# Scheme.net
KiCad netlist of a schematic drawn in Altium Designer
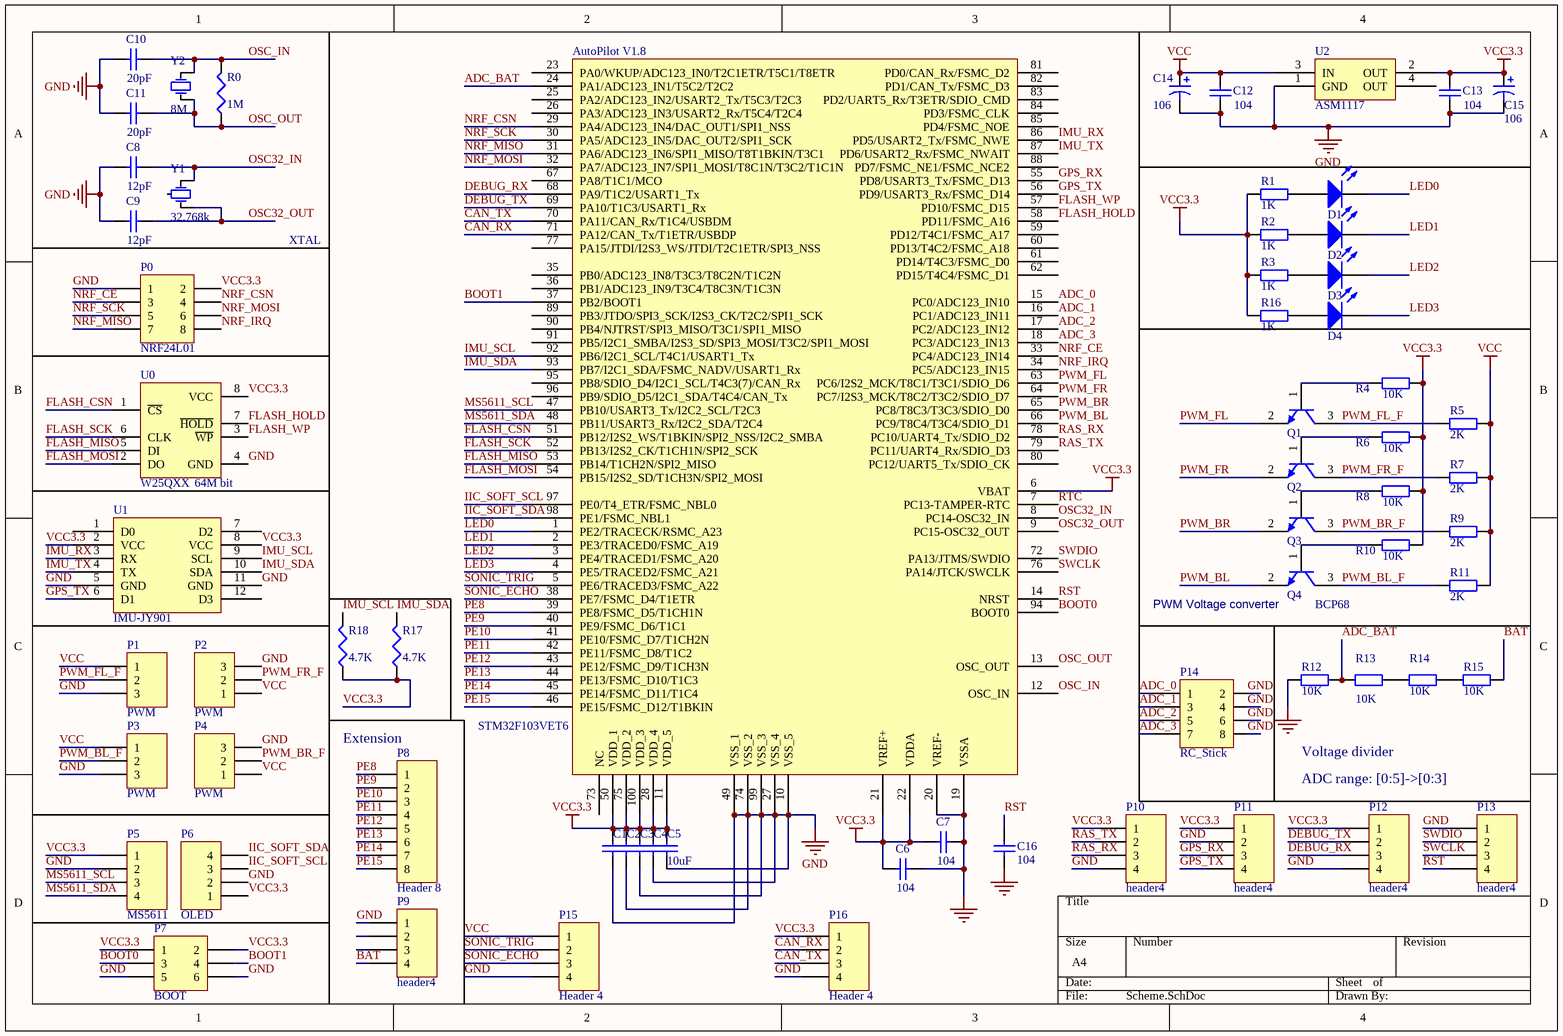
[diagram p0: Scheme.SchDoc]

(export (version "E")
  (design (tool "Eeschema 10.0.6"))
  (components
    (comp (ref "AutoPilot V1.8")
      (value "STM32F103VET6")
      (footprint "LQFP-100_M")
      (description "STM32单片机100引脚")
      (libsource (lib "LYY") (part "STM32F103V"))
    )
    (comp (ref "C1")
      (value "Cap Semi")
      (footprint "1608[0603]")
      (description "Capacitor (Semiconductor SIM Model)")
      (fields (field (name "PUBLISHER") "Altium Limited"))
      (libsource (lib "Miscellaneous Devices") (part "Cap Semi"))
    )
    (comp (ref "C2")
      (value "Cap Semi")
      (footprint "1608[0603]")
      (description "Capacitor (Semiconductor SIM Model)")
      (fields (field (name "PUBLISHER") "Altium Limited"))
      (libsource (lib "Miscellaneous Devices") (part "Cap Semi"))
    )
    (comp (ref "C3")
      (value "Cap Semi")
      (footprint "1608[0603]")
      (description "Capacitor (Semiconductor SIM Model)")
      (fields (field (name "PUBLISHER") "Altium Limited"))
      (libsource (lib "Miscellaneous Devices") (part "Cap Semi"))
    )
    (comp (ref "C4")
      (value "Cap Semi")
      (footprint "1608[0603]")
      (description "Capacitor (Semiconductor SIM Model)")
      (fields (field (name "PUBLISHER") "Altium Limited"))
      (libsource (lib "Miscellaneous Devices") (part "Cap Semi"))
    )
    (comp (ref "C5")
      (value "10uF")
      (footprint "1608[0603]")
      (description "Capacitor (Semiconductor SIM Model)")
      (fields (field (name "Comment") "Cap Semi") (field (name "PUBLISHER") "Altium Limited"))
      (libsource (lib "Miscellaneous Devices") (part "Cap Semi"))
    )
    (comp (ref "C6")
      (value "104")
      (footprint "1608[0603]")
      (description "Capacitor (Semiconductor SIM Model)")
      (fields (field (name "Comment") "Cap Semi") (field (name "PUBLISHER") "Altium Limited"))
      (libsource (lib "Miscellaneous Devices") (part "Cap Semi"))
    )
    (comp (ref "C7")
      (value "104")
      (footprint "1608[0603]")
      (description "Capacitor (Semiconductor SIM Model)")
      (fields (field (name "Comment") "Cap Semi") (field (name "PUBLISHER") "Altium Limited"))
      (libsource (lib "Miscellaneous Devices") (part "Cap Semi"))
    )
    (comp (ref "C8")
      (value "12pF")
      (footprint "1608[0603]")
      (description "Capacitor (Semiconductor SIM Model)")
      (fields (field (name "Comment") "Cap Semi") (field (name "PUBLISHER") "Altium Limited"))
      (libsource (lib "Miscellaneous Devices") (part "Cap Semi"))
    )
    (comp (ref "C9")
      (value "12pF")
      (footprint "1608[0603]")
      (description "Capacitor (Semiconductor SIM Model)")
      (fields (field (name "Comment") "Cap Semi") (field (name "PUBLISHER") "Altium Limited"))
      (libsource (lib "Miscellaneous Devices") (part "Cap Semi"))
    )
    (comp (ref "C10")
      (value "20pF")
      (footprint "1608[0603]")
      (description "Capacitor (Semiconductor SIM Model)")
      (fields (field (name "Comment") "Cap Semi") (field (name "PUBLISHER") "Altium Limited"))
      (libsource (lib "Miscellaneous Devices") (part "Cap Semi"))
    )
    (comp (ref "C11")
      (value "20pF")
      (footprint "1608[0603]")
      (description "Capacitor (Semiconductor SIM Model)")
      (fields (field (name "Comment") "Cap Semi") (field (name "PUBLISHER") "Altium Limited"))
      (libsource (lib "Miscellaneous Devices") (part "Cap Semi"))
    )
    (comp (ref "C12")
      (value "104")
      (footprint "1608[0603]")
      (description "Capacitor (Semiconductor SIM Model)")
      (fields (field (name "Comment") "Cap Semi") (field (name "PUBLISHER") "Altium Limited"))
      (libsource (lib "Miscellaneous Devices") (part "Cap Semi"))
    )
    (comp (ref "C13")
      (value "104")
      (footprint "1608[0603]")
      (description "Capacitor (Semiconductor SIM Model)")
      (fields (field (name "Comment") "Cap Semi") (field (name "PUBLISHER") "Altium Limited"))
      (libsource (lib "Miscellaneous Devices") (part "Cap Semi"))
    )
    (comp (ref "C14")
      (value "106")
      (footprint "1812")
      (description "Polarized Capacitor (Surface Mount)")
      (fields (field (name "Comment") "Cap Pol3") (field (name "PUBLISHER") "Altium Limited"))
      (libsource (lib "Miscellaneous Devices") (part "Cap Pol3"))
    )
    (comp (ref "C15")
      (value "106")
      (footprint "1812")
      (description "Polarized Capacitor (Surface Mount)")
      (fields (field (name "Comment") "Cap Pol3") (field (name "PUBLISHER") "Altium Limited"))
      (libsource (lib "Miscellaneous Devices") (part "Cap Pol3"))
    )
    (comp (ref "C16")
      (value "104")
      (footprint "1608[0603]")
      (description "Capacitor (Semiconductor SIM Model)")
      (fields (field (name "Comment") "Cap Semi") (field (name "PUBLISHER") "Altium Limited"))
      (libsource (lib "Miscellaneous Devices") (part "Cap Semi"))
    )
    (comp (ref "D1")
      (value "LED0")
      (footprint "LED_0805")
      (description "发光二极管")
      (fields (field (name "PUBLISHER") "Altium Limited"))
      (libsource (lib "LYY") (part "LED0"))
    )
    (comp (ref "D2")
      (value "LED0")
      (footprint "LED_0805")
      (description "发光二极管")
      (fields (field (name "PUBLISHER") "Altium Limited"))
      (libsource (lib "LYY") (part "LED0"))
    )
    (comp (ref "D3")
      (value "LED0")
      (footprint "LED_0805")
      (description "发光二极管")
      (fields (field (name "PUBLISHER") "Altium Limited"))
      (libsource (lib "LYY") (part "LED0"))
    )
    (comp (ref "D4")
      (value "LED0")
      (footprint "LED_0805")
      (description "发光二极管")
      (fields (field (name "PUBLISHER") "Altium Limited"))
      (libsource (lib "LYY") (part "LED0"))
    )
    (comp (ref "P0")
      (value "NRF24L01")
      (footprint "HDR2X4")
      (description "Header, 4-Pin, Dual row")
      (fields (field (name "PUBLISHER") "Altium Limited"))
      (libsource (lib "Miscellaneous Connectors") (part "Header 4X2"))
    )
    (comp (ref "P1")
      (value "PWM")
      (footprint "HDR1X3")
      (description "Header, 3-Pin")
      (fields (field (name "PUBLISHER") "Altium Limited"))
      (libsource (lib "Miscellaneous Connectors") (part "Header 3"))
    )
    (comp (ref "P2")
      (value "PWM")
      (footprint "HDR1X3")
      (description "Header, 3-Pin")
      (fields (field (name "PUBLISHER") "Altium Limited"))
      (libsource (lib "") (part "Header 3_1"))
    )
    (comp (ref "P3")
      (value "PWM")
      (footprint "HDR1X3")
      (description "Header, 3-Pin")
      (fields (field (name "PUBLISHER") "Altium Limited"))
      (libsource (lib "Miscellaneous Connectors") (part "Header 3"))
    )
    (comp (ref "P4")
      (value "PWM")
      (footprint "HDR1X3")
      (description "Header, 3-Pin")
      (fields (field (name "PUBLISHER") "Altium Limited"))
      (libsource (lib "") (part "Header 3_1"))
    )
    (comp (ref "P5")
      (value "MS5611")
      (footprint "HDR1X4")
      (description "Header, 4-Pin")
      (fields (field (name "PUBLISHER") "Altium Limited"))
      (libsource (lib "Miscellaneous Connectors") (part "Header 4"))
    )
    (comp (ref "P6")
      (value "OLED")
      (footprint "HDR1X4")
      (description "Header, 4-Pin")
      (fields (field (name "PUBLISHER") "Altium Limited"))
      (libsource (lib "") (part "Header 4_1"))
    )
    (comp (ref "P7")
      (value "BOOT")
      (footprint "HDR2X3")
      (description "Header, 3-Pin, Dual row")
      (fields (field (name "PUBLISHER") "Altium Limited"))
      (libsource (lib "Miscellaneous Connectors") (part "Header 3X2"))
    )
    (comp (ref "P8")
      (value "Header 8")
      (footprint "HDR1X8")
      (description "Header, 8-Pin")
      (fields (field (name "PUBLISHER") "Altium Limited"))
      (libsource (lib "Miscellaneous Connectors") (part "Header 8"))
    )
    (comp (ref "P9")
      (value "header4")
      (footprint "HDR1X4")
      (description "Header, 4-Pin")
      (fields (field (name "PUBLISHER") "Altium Limited"))
      (libsource (lib "Miscellaneous Connectors") (part "Header 4"))
    )
    (comp (ref "P10")
      (value "header4")
      (footprint "HDR1X4")
      (description "Header, 4-Pin")
      (fields (field (name "PUBLISHER") "Altium Limited"))
      (libsource (lib "Miscellaneous Connectors") (part "Header 4"))
    )
    (comp (ref "P11")
      (value "header4")
      (footprint "HDR1X4")
      (description "Header, 4-Pin")
      (fields (field (name "PUBLISHER") "Altium Limited"))
      (libsource (lib "Miscellaneous Connectors") (part "Header 4"))
    )
    (comp (ref "P12")
      (value "header4")
      (footprint "HDR1X4")
      (description "Header, 4-Pin")
      (fields (field (name "PUBLISHER") "Altium Limited"))
      (libsource (lib "Miscellaneous Connectors") (part "Header 4"))
    )
    (comp (ref "P13")
      (value "header4")
      (footprint "HDR1X4")
      (description "Header, 4-Pin")
      (fields (field (name "PUBLISHER") "Altium Limited"))
      (libsource (lib "Miscellaneous Connectors") (part "Header 4"))
    )
    (comp (ref "P14")
      (value "RC_Stick")
      (footprint "HDR2X4")
      (description "Header, 4-Pin, Dual row")
      (fields (field (name "PUBLISHER") "Altium Limited"))
      (libsource (lib "Miscellaneous Connectors") (part "Header 4X2"))
    )
    (comp (ref "P15")
      (value "Header 4")
      (footprint "HDR1X4")
      (description "Header, 4-Pin")
      (fields (field (name "PUBLISHER") "Altium Limited"))
      (libsource (lib "Miscellaneous Connectors") (part "Header 4"))
    )
    (comp (ref "P16")
      (value "Header 4")
      (footprint "HDR1X4")
      (description "Header, 4-Pin")
      (fields (field (name "PUBLISHER") "Altium Limited"))
      (libsource (lib "Miscellaneous Connectors") (part "Header 4"))
    )
    (comp (ref "Q1")
      (value "BCP68")
      (footprint "SOT-23")
      (description "NPN三极管")
      (fields (field (name "PUBLISHER") "Altium Limited"))
      (libsource (lib "LYY") (part "BCP68"))
    )
    (comp (ref "Q2")
      (value "BCP68")
      (footprint "SOT-23")
      (description "NPN三极管")
      (fields (field (name "PUBLISHER") "Altium Limited"))
      (libsource (lib "LYY") (part "BCP68"))
    )
    (comp (ref "Q3")
      (value "BCP68")
      (footprint "SOT-23")
      (description "NPN三极管")
      (fields (field (name "PUBLISHER") "Altium Limited"))
      (libsource (lib "LYY") (part "BCP68"))
    )
    (comp (ref "Q4")
      (value "BCP68")
      (footprint "SOT-23")
      (description "NPN三极管")
      (fields (field (name "PUBLISHER") "Altium Limited"))
      (libsource (lib "LYY") (part "BCP68"))
    )
    (comp (ref "R0")
      (value "1M")
      (footprint "0603-1")
      (description "Resistor")
      (fields (field (name "Comment") "Res3") (field (name "PUBLISHER") "Altium Limited"))
      (libsource (lib "Miscellaneous Devices") (part "Res3"))
    )
    (comp (ref "R1")
      (value "1K")
      (footprint "0603-1")
      (description "贴片电阻")
      (fields (field (name "Comment") "Res1") (field (name "PUBLISHER") "Altium Limited"))
      (libsource (lib "LYY") (part "Res1"))
    )
    (comp (ref "R2")
      (value "1K")
      (footprint "0603-1")
      (description "贴片电阻")
      (fields (field (name "Comment") "Res1") (field (name "PUBLISHER") "Altium Limited"))
      (libsource (lib "LYY") (part "Res1"))
    )
    (comp (ref "R3")
      (value "1K")
      (footprint "0603-1")
      (description "贴片电阻")
      (fields (field (name "Comment") "Res1") (field (name "PUBLISHER") "Altium Limited"))
      (libsource (lib "LYY") (part "Res1"))
    )
    (comp (ref "R4")
      (value "10K")
      (footprint "0603-1")
      (description "贴片电阻")
      (fields (field (name "Comment") "Res1") (field (name "PUBLISHER") "Altium Limited"))
      (libsource (lib "LYY") (part "Res1"))
    )
    (comp (ref "R5")
      (value "2K")
      (footprint "0603-1")
      (description "贴片电阻")
      (fields (field (name "Comment") "Res1") (field (name "PUBLISHER") "Altium Limited"))
      (libsource (lib "LYY") (part "Res1"))
    )
    (comp (ref "R6")
      (value "10K")
      (footprint "0603-1")
      (description "贴片电阻")
      (fields (field (name "Comment") "Res1") (field (name "PUBLISHER") "Altium Limited"))
      (libsource (lib "LYY") (part "Res1"))
    )
    (comp (ref "R7")
      (value "2K")
      (footprint "0603-1")
      (description "贴片电阻")
      (fields (field (name "Comment") "Res1") (field (name "PUBLISHER") "Altium Limited"))
      (libsource (lib "LYY") (part "Res1"))
    )
    (comp (ref "R8")
      (value "10K")
      (footprint "0603-1")
      (description "贴片电阻")
      (fields (field (name "Comment") "Res1") (field (name "PUBLISHER") "Altium Limited"))
      (libsource (lib "LYY") (part "Res1"))
    )
    (comp (ref "R9")
      (value "2K")
      (footprint "0603-1")
      (description "贴片电阻")
      (fields (field (name "Comment") "Res1") (field (name "PUBLISHER") "Altium Limited"))
      (libsource (lib "LYY") (part "Res1"))
    )
    (comp (ref "R10")
      (value "10K")
      (footprint "0603-1")
      (description "贴片电阻")
      (fields (field (name "Comment") "Res1") (field (name "PUBLISHER") "Altium Limited"))
      (libsource (lib "LYY") (part "Res1"))
    )
    (comp (ref "R11")
      (value "2K")
      (footprint "0603-1")
      (description "贴片电阻")
      (fields (field (name "Comment") "Res1") (field (name "PUBLISHER") "Altium Limited"))
      (libsource (lib "LYY") (part "Res1"))
    )
    (comp (ref "R12")
      (value "10K")
      (footprint "0603-1")
      (description "贴片电阻")
      (fields (field (name "Comment") "Res1") (field (name "PUBLISHER") "Altium Limited"))
      (libsource (lib "LYY") (part "Res1"))
    )
    (comp (ref "R13")
      (value "10K")
      (footprint "0603-1")
      (description "贴片电阻")
      (fields (field (name "PUBLISHER") "Altium Limited"))
      (libsource (lib "LYY") (part "Res1"))
    )
    (comp (ref "R14")
      (value "10K")
      (footprint "0603-1")
      (description "贴片电阻")
      (fields (field (name "Comment") "Res1") (field (name "PUBLISHER") "Altium Limited"))
      (libsource (lib "LYY") (part "Res1"))
    )
    (comp (ref "R15")
      (value "10K")
      (footprint "0603-1")
      (description "贴片电阻")
      (fields (field (name "Comment") "Res1") (field (name "PUBLISHER") "Altium Limited"))
      (libsource (lib "LYY") (part "Res1"))
    )
    (comp (ref "R16")
      (value "1K")
      (footprint "0603-1")
      (description "贴片电阻")
      (fields (field (name "Comment") "Res1") (field (name "PUBLISHER") "Altium Limited"))
      (libsource (lib "LYY") (part "Res1"))
    )
    (comp (ref "R17")
      (value "4.7K")
      (footprint "14-1210")
      (description "Resistor")
      (fields (field (name "PUBLISHER") "Altium Limited"))
      (libsource (lib "Miscellaneous Devices") (part "Res3"))
    )
    (comp (ref "R18")
      (value "4.7K")
      (footprint "14-1210")
      (description "Resistor")
      (fields (field (name "PUBLISHER") "Altium Limited"))
      (libsource (lib "Miscellaneous Devices") (part "Res3"))
    )
    (comp (ref "U0")
      (value "W25QXX")
      (footprint "SOIC8_W")
      (description "SPI FLASH")
      (fields (field (name "MEMORY") "64M bit"))
      (libsource (lib "LYY") (part "W25QXX"))
    )
    (comp (ref "U1") (value "IMU-JY901") (footprint "JY901:JY-901") (libsource (lib "JY901") (part "JY901")))
    (comp (ref "U2")
      (value "ASM1117")
      (footprint "SOT-223")
      (description "3.3V稳压芯片")
      (libsource (lib "LYY") (part "ASM1117"))
    )
    (comp (ref "Y1")
      (value "32.768k")
      (footprint "X-2X6C - duplicate")
      (description "圆柱晶振")
      (fields (field (name "Comment") "XTAL_SM") (field (name "PUBLISHER") "Altium Limited"))
      (libsource (lib "LYY") (part "XTAL_SM"))
    )
    (comp (ref "Y2")
      (value "8M")
      (footprint "X-HC49U")
      (description "晶振")
      (fields (field (name "Comment") "XTAL") (field (name "PUBLISHER") "Altium Limited"))
      (libsource (lib "LYY") (part "XTAL"))
    )
  )
  (nets
    (net (code "1") (name "/ADC_0") (class "Default")
      (node (ref "AutoPilot V1.8") (pin "15") (pinfunction "PC0/ADC123_IN10_15") (pintype "passive"))
      (node (ref "P14") (pin "1") (pinfunction "1_1") (pintype "passive"))
    )
    (net (code "2") (name "/ADC_1") (class "Default")
      (node (ref "AutoPilot V1.8") (pin "16") (pinfunction "PC1/ADC123_IN11_16") (pintype "passive"))
      (node (ref "P14") (pin "3") (pinfunction "3_3") (pintype "passive"))
    )
    (net (code "3") (name "/ADC_2") (class "Default")
      (node (ref "AutoPilot V1.8") (pin "17") (pinfunction "PC2/ADC123_IN12_17") (pintype "passive"))
      (node (ref "P14") (pin "5") (pinfunction "5_5") (pintype "passive"))
    )
    (net (code "4") (name "/ADC_3") (class "Default")
      (node (ref "AutoPilot V1.8") (pin "18") (pinfunction "PC3/ADC123_IN13_18") (pintype "passive"))
      (node (ref "P14") (pin "7") (pinfunction "7_7") (pintype "passive"))
    )
    (net (code "5") (name "/ADC_BAT") (class "Default")
      (node (ref "AutoPilot V1.8") (pin "24") (pinfunction "PA1/ADC123_IN1/T5C2/T2C2_24") (pintype "passive"))
      (node (ref "R12") (pin "2") (pinfunction "2_2") (pintype "passive"))
      (node (ref "R13") (pin "1") (pinfunction "1_1") (pintype "passive"))
    )
    (net (code "6") (name "/BAT") (class "Default")
      (node (ref "P9") (pin "4") (pinfunction "4_4") (pintype "passive"))
      (node (ref "R15") (pin "2") (pinfunction "2_2") (pintype "passive"))
    )
    (net (code "7") (name "/BOOT0") (class "Default")
      (node (ref "AutoPilot V1.8") (pin "94") (pinfunction "BOOT0_94") (pintype "passive"))
      (node (ref "P7") (pin "3") (pinfunction "3_3") (pintype "passive"))
    )
    (net (code "8") (name "/BOOT1") (class "Default")
      (node (ref "AutoPilot V1.8") (pin "37") (pinfunction "PB2/BOOT1_37") (pintype "passive"))
      (node (ref "P7") (pin "4") (pinfunction "4_4") (pintype "passive"))
    )
    (net (code "9") (name "/CAN_RX") (class "Default")
      (node (ref "AutoPilot V1.8") (pin "71") (pinfunction "PA12/CAN_Tx/T1ETR/USBDP_71") (pintype "passive"))
      (node (ref "P16") (pin "2") (pinfunction "2_2") (pintype "passive"))
    )
    (net (code "10") (name "/CAN_TX") (class "Default")
      (node (ref "AutoPilot V1.8") (pin "70") (pinfunction "PA11/CAN_Rx/T1C4/USBDM_70") (pintype "passive"))
      (node (ref "P16") (pin "3") (pinfunction "3_3") (pintype "passive"))
    )
    (net (code "11") (name "/DEBUG_RX") (class "Default")
      (node (ref "AutoPilot V1.8") (pin "68") (pinfunction "PA9/T1C2/USART1_Tx_68") (pintype "passive"))
      (node (ref "P12") (pin "3") (pinfunction "3_3") (pintype "passive"))
    )
    (net (code "12") (name "/DEBUG_TX") (class "Default")
      (node (ref "AutoPilot V1.8") (pin "69") (pinfunction "PA10/T1C3/USART1_Rx_69") (pintype "passive"))
      (node (ref "P12") (pin "2") (pinfunction "2_2") (pintype "passive"))
    )
    (net (code "13") (name "/FLASH_CSN") (class "Default")
      (node (ref "AutoPilot V1.8") (pin "51") (pinfunction "PB12/I2S2_WS/T1BKIN/SPI2_NSS/I2C2_SMBA_51") (pintype "passive"))
      (node (ref "U0") (pin "1") (pinfunction "~{CS}_1") (pintype "passive"))
    )
    (net (code "14") (name "/FLASH_HOLD") (class "Default")
      (node (ref "AutoPilot V1.8") (pin "58") (pinfunction "PD11/FSMC_A16_58") (pintype "passive"))
      (node (ref "U0") (pin "7") (pinfunction "~{HOLD}_7") (pintype "passive"))
    )
    (net (code "15") (name "/FLASH_MISO") (class "Default")
      (node (ref "AutoPilot V1.8") (pin "53") (pinfunction "PB14/T1CH2N/SPI2_MISO_53") (pintype "passive"))
      (node (ref "U0") (pin "5") (pinfunction "DI_5") (pintype "passive"))
    )
    (net (code "16") (name "/FLASH_MOSI") (class "Default")
      (node (ref "AutoPilot V1.8") (pin "54") (pinfunction "PB15/I2S2_SD/T1CH3N/SPI2_MOSI_54") (pintype "passive"))
      (node (ref "U0") (pin "2") (pinfunction "DO_2") (pintype "passive"))
    )
    (net (code "17") (name "/FLASH_SCK") (class "Default")
      (node (ref "AutoPilot V1.8") (pin "52") (pinfunction "PB13/I2S2_CK/T1CH1N/SPI2_SCK_52") (pintype "passive"))
      (node (ref "U0") (pin "6") (pinfunction "CLK_6") (pintype "passive"))
    )
    (net (code "18") (name "/FLASH_WP") (class "Default")
      (node (ref "AutoPilot V1.8") (pin "57") (pinfunction "PD10/FSMC_D15_57") (pintype "passive"))
      (node (ref "U0") (pin "3") (pinfunction "~{WP}_3") (pintype "passive"))
    )
    (net (code "19") (name "/GPS_RX") (class "Default")
      (node (ref "AutoPilot V1.8") (pin "55") (pinfunction "PD8/USART3_Tx/FSMC_D13_55") (pintype "passive"))
      (node (ref "P11") (pin "3") (pinfunction "3_3") (pintype "passive"))
    )
    (net (code "20") (name "/GPS_TX") (class "Default")
      (node (ref "AutoPilot V1.8") (pin "56") (pinfunction "PD9/USART3_Rx/FSMC_D14_56") (pintype "passive"))
      (node (ref "P11") (pin "4") (pinfunction "4_4") (pintype "passive"))
      (node (ref "U1") (pin "6") (pinfunction "D1_6") (pintype "passive"))
    )
    (net (code "21") (name "/IIC_SOFT_SCL") (class "Default")
      (node (ref "AutoPilot V1.8") (pin "97") (pinfunction "PE0/T4_ETR/FSMC_NBL0_97") (pintype "passive"))
      (node (ref "P6") (pin "3") (pinfunction "3_3") (pintype "passive"))
    )
    (net (code "22") (name "/IIC_SOFT_SDA") (class "Default")
      (node (ref "AutoPilot V1.8") (pin "98") (pinfunction "PE1/FSMC_NBL1_98") (pintype "passive"))
      (node (ref "P6") (pin "4") (pinfunction "4_4") (pintype "passive"))
    )
    (net (code "23") (name "/IMU_RX") (class "Default")
      (node (ref "AutoPilot V1.8") (pin "86") (pinfunction "PD5/USART2_Tx/FSMC_NWE_86") (pintype "passive"))
      (node (ref "U1") (pin "3") (pinfunction "RX_3") (pintype "passive"))
    )
    (net (code "24") (name "/IMU_SCL") (class "Default")
      (node (ref "AutoPilot V1.8") (pin "92") (pinfunction "PB6/I2C1_SCL/T4C1/USART1_Tx_92") (pintype "passive"))
      (node (ref "R18") (pin "2") (pinfunction "2_2") (pintype "passive"))
      (node (ref "U1") (pin "9") (pinfunction "SCL_9") (pintype "passive"))
    )
    (net (code "25") (name "/IMU_SDA") (class "Default")
      (node (ref "AutoPilot V1.8") (pin "93") (pinfunction "PB7/I2C1_SDA/FSMC_NADV/USART1_Rx_93") (pintype "passive"))
      (node (ref "R17") (pin "2") (pinfunction "2_2") (pintype "passive"))
      (node (ref "U1") (pin "10") (pinfunction "SDA_10") (pintype "passive"))
    )
    (net (code "26") (name "/IMU_TX") (class "Default")
      (node (ref "AutoPilot V1.8") (pin "87") (pinfunction "PD6/USART2_Rx/FSMC_NWAIT_87") (pintype "passive"))
      (node (ref "U1") (pin "4") (pinfunction "TX_4") (pintype "passive"))
    )
    (net (code "27") (name "/LED0") (class "Default")
      (node (ref "AutoPilot V1.8") (pin "1") (pinfunction "PE2/TRACECK/RSMC_A23_1") (pintype "passive"))
      (node (ref "D1") (pin "2") (pinfunction "K_2") (pintype "passive"))
    )
    (net (code "28") (name "/LED1") (class "Default")
      (node (ref "AutoPilot V1.8") (pin "2") (pinfunction "PE3/TRACED0/FSMC_A19_2") (pintype "passive"))
      (node (ref "D2") (pin "2") (pinfunction "K_2") (pintype "passive"))
    )
    (net (code "29") (name "/LED2") (class "Default")
      (node (ref "AutoPilot V1.8") (pin "3") (pinfunction "PE4/TRACED1/FSMC_A20_3") (pintype "passive"))
      (node (ref "D3") (pin "2") (pinfunction "K_2") (pintype "passive"))
    )
    (net (code "30") (name "/LED3") (class "Default")
      (node (ref "AutoPilot V1.8") (pin "4") (pinfunction "PE5/TRACED2/FSMC_A21_4") (pintype "passive"))
      (node (ref "D4") (pin "2") (pinfunction "K_2") (pintype "passive"))
    )
    (net (code "31") (name "/MS5611_SCL") (class "Default")
      (node (ref "AutoPilot V1.8") (pin "47") (pinfunction "PB10/USART3_Tx/I2C2_SCL/T2C3_47") (pintype "passive"))
      (node (ref "P5") (pin "3") (pinfunction "3_3") (pintype "passive"))
    )
    (net (code "32") (name "/MS5611_SDA") (class "Default")
      (node (ref "AutoPilot V1.8") (pin "48") (pinfunction "PB11/USART3_Rx/I2C2_SDA/T2C4_48") (pintype "passive"))
      (node (ref "P5") (pin "4") (pinfunction "4_4") (pintype "passive"))
    )
    (net (code "33") (name "/NRF_CE") (class "Default")
      (node (ref "AutoPilot V1.8") (pin "33") (pinfunction "PC4/ADC123_IN14_33") (pintype "passive"))
      (node (ref "P0") (pin "3") (pinfunction "3_3") (pintype "passive"))
    )
    (net (code "34") (name "/NRF_CSN") (class "Default")
      (node (ref "AutoPilot V1.8") (pin "29") (pinfunction "PA4/ADC123_IN4/DAC_OUT1/SPI1_NSS_29") (pintype "passive"))
      (node (ref "P0") (pin "4") (pinfunction "4_4") (pintype "passive"))
    )
    (net (code "35") (name "/NRF_IRQ") (class "Default")
      (node (ref "AutoPilot V1.8") (pin "34") (pinfunction "PC5/ADC123_IN15_34") (pintype "passive"))
      (node (ref "P0") (pin "8") (pinfunction "8_8") (pintype "passive"))
    )
    (net (code "36") (name "/NRF_MISO") (class "Default")
      (node (ref "AutoPilot V1.8") (pin "31") (pinfunction "PA6/ADC123_IN6/SPI1_MISO/T8T1BKIN/T3C1_31") (pintype "passive"))
      (node (ref "P0") (pin "7") (pinfunction "7_7") (pintype "passive"))
    )
    (net (code "37") (name "/NRF_MOSI") (class "Default")
      (node (ref "AutoPilot V1.8") (pin "32") (pinfunction "PA7/ADC123_IN7/SPI1_MOSI/T8C1N/T3C2/T1C1N_32") (pintype "passive"))
      (node (ref "P0") (pin "6") (pinfunction "6_6") (pintype "passive"))
    )
    (net (code "38") (name "/NRF_SCK") (class "Default")
      (node (ref "AutoPilot V1.8") (pin "30") (pinfunction "PA5/ADC123_IN5/DAC_OUT2/SPI1_SCK_30") (pintype "passive"))
      (node (ref "P0") (pin "5") (pinfunction "5_5") (pintype "passive"))
    )
    (net (code "39") (name "/OSC32_IN") (class "Default")
      (node (ref "AutoPilot V1.8") (pin "8") (pinfunction "PC14-OSC32_IN_8") (pintype "passive"))
      (node (ref "C8") (pin "2") (pinfunction "2_2") (pintype "passive"))
      (node (ref "Y1") (pin "1") (pinfunction "OSC1_1") (pintype "passive"))
    )
    (net (code "40") (name "/OSC32_OUT") (class "Default")
      (node (ref "AutoPilot V1.8") (pin "9") (pinfunction "PC15-OSC32_OUT_9") (pintype "passive"))
      (node (ref "C9") (pin "2") (pinfunction "2_2") (pintype "passive"))
      (node (ref "Y1") (pin "2") (pinfunction "OSC2_2") (pintype "passive"))
    )
    (net (code "41") (name "/OSC_IN") (class "Default")
      (node (ref "AutoPilot V1.8") (pin "12") (pinfunction "OSC_IN_12") (pintype "passive"))
      (node (ref "C10") (pin "2") (pinfunction "2_2") (pintype "passive"))
      (node (ref "R0") (pin "2") (pinfunction "2_2") (pintype "passive"))
      (node (ref "Y2") (pin "2") (pinfunction "OSC2_2") (pintype "passive"))
    )
    (net (code "42") (name "/OSC_OUT") (class "Default")
      (node (ref "AutoPilot V1.8") (pin "13") (pinfunction "OSC_OUT_13") (pintype "passive"))
      (node (ref "C11") (pin "2") (pinfunction "2_2") (pintype "passive"))
      (node (ref "R0") (pin "1") (pinfunction "1_1") (pintype "passive"))
      (node (ref "Y2") (pin "1") (pinfunction "OSC1_1") (pintype "passive"))
    )
    (net (code "43") (name "/PE8") (class "Default")
      (node (ref "AutoPilot V1.8") (pin "39") (pinfunction "PE8/FSMC_D5/T1CH1N_39") (pintype "passive"))
      (node (ref "P8") (pin "1") (pinfunction "1_1") (pintype "passive"))
    )
    (net (code "44") (name "/PE9") (class "Default")
      (node (ref "AutoPilot V1.8") (pin "40") (pinfunction "PE9/FSMC_D6/T1C1_40") (pintype "passive"))
      (node (ref "P8") (pin "2") (pinfunction "2_2") (pintype "passive"))
    )
    (net (code "45") (name "/PE10") (class "Default")
      (node (ref "AutoPilot V1.8") (pin "41") (pinfunction "PE10/FSMC_D7/T1CH2N_41") (pintype "passive"))
      (node (ref "P8") (pin "3") (pinfunction "3_3") (pintype "passive"))
    )
    (net (code "46") (name "/PE11") (class "Default")
      (node (ref "AutoPilot V1.8") (pin "42") (pinfunction "PE11/FSMC_D8/T1C2_42") (pintype "passive"))
      (node (ref "P8") (pin "4") (pinfunction "4_4") (pintype "passive"))
    )
    (net (code "47") (name "/PE12") (class "Default")
      (node (ref "AutoPilot V1.8") (pin "43") (pinfunction "PE12/FSMC_D9/T1CH3N_43") (pintype "passive"))
      (node (ref "P8") (pin "5") (pinfunction "5_5") (pintype "passive"))
    )
    (net (code "48") (name "/PE13") (class "Default")
      (node (ref "AutoPilot V1.8") (pin "44") (pinfunction "PE13/FSMC_D10/T1C3_44") (pintype "passive"))
      (node (ref "P8") (pin "6") (pinfunction "6_6") (pintype "passive"))
    )
    (net (code "49") (name "/PE14") (class "Default")
      (node (ref "AutoPilot V1.8") (pin "45") (pinfunction "PE14/FSMC_D11/T1C4_45") (pintype "passive"))
      (node (ref "P8") (pin "7") (pinfunction "7_7") (pintype "passive"))
    )
    (net (code "50") (name "/PE15") (class "Default")
      (node (ref "AutoPilot V1.8") (pin "46") (pinfunction "PE15/FSMC_D12/T1BKIN_46") (pintype "passive"))
      (node (ref "P8") (pin "8") (pinfunction "8_8") (pintype "passive"))
    )
    (net (code "51") (name "/PWM_BL") (class "Default")
      (node (ref "AutoPilot V1.8") (pin "66") (pinfunction "PC9/T8C4/T3C4/SDIO_D1_66") (pintype "passive"))
      (node (ref "Q4") (pin "2") (pinfunction "E_2") (pintype "passive"))
    )
    (net (code "52") (name "/PWM_BL_F") (class "Default")
      (node (ref "P3") (pin "2") (pinfunction "2_2") (pintype "passive"))
      (node (ref "Q4") (pin "3") (pinfunction "C_3") (pintype "passive"))
      (node (ref "R11") (pin "1") (pinfunction "1_1") (pintype "passive"))
    )
    (net (code "53") (name "/PWM_BR") (class "Default")
      (node (ref "AutoPilot V1.8") (pin "65") (pinfunction "PC8/T8C3/T3C3/SDIO_D0_65") (pintype "passive"))
      (node (ref "Q3") (pin "2") (pinfunction "E_2") (pintype "passive"))
    )
    (net (code "54") (name "/PWM_BR_F") (class "Default")
      (node (ref "P4") (pin "2") (pinfunction "2_2") (pintype "passive"))
      (node (ref "Q3") (pin "3") (pinfunction "C_3") (pintype "passive"))
      (node (ref "R9") (pin "1") (pinfunction "1_1") (pintype "passive"))
    )
    (net (code "55") (name "/PWM_FL") (class "Default")
      (node (ref "AutoPilot V1.8") (pin "63") (pinfunction "PC6/I2S2_MCK/T8C1/T3C1/SDIO_D6_63") (pintype "passive"))
      (node (ref "Q1") (pin "2") (pinfunction "E_2") (pintype "passive"))
    )
    (net (code "56") (name "/PWM_FL_F") (class "Default")
      (node (ref "P1") (pin "2") (pinfunction "2_2") (pintype "passive"))
      (node (ref "Q1") (pin "3") (pinfunction "C_3") (pintype "passive"))
      (node (ref "R5") (pin "1") (pinfunction "1_1") (pintype "passive"))
    )
    (net (code "57") (name "/PWM_FR") (class "Default")
      (node (ref "AutoPilot V1.8") (pin "64") (pinfunction "PC7/I2S3_MCK/T8C2/T3C2/SDIO_D7_64") (pintype "passive"))
      (node (ref "Q2") (pin "2") (pinfunction "E_2") (pintype "passive"))
    )
    (net (code "58") (name "/PWM_FR_F") (class "Default")
      (node (ref "P2") (pin "2") (pinfunction "2_2") (pintype "passive"))
      (node (ref "Q2") (pin "3") (pinfunction "C_3") (pintype "passive"))
      (node (ref "R7") (pin "1") (pinfunction "1_1") (pintype "passive"))
    )
    (net (code "59") (name "/RAS_RX") (class "Default")
      (node (ref "AutoPilot V1.8") (pin "78") (pinfunction "PC10/UART4_Tx/SDIO_D2_78") (pintype "passive"))
      (node (ref "P10") (pin "3") (pinfunction "3_3") (pintype "passive"))
    )
    (net (code "60") (name "/RAS_TX") (class "Default")
      (node (ref "AutoPilot V1.8") (pin "79") (pinfunction "PC11/UART4_Rx/SDIO_D3_79") (pintype "passive"))
      (node (ref "P10") (pin "2") (pinfunction "2_2") (pintype "passive"))
    )
    (net (code "61") (name "/RST") (class "Default")
      (node (ref "AutoPilot V1.8") (pin "14") (pinfunction "NRST_14") (pintype "passive"))
      (node (ref "C16") (pin "1") (pinfunction "1_1") (pintype "passive"))
      (node (ref "P13") (pin "4") (pinfunction "4_4") (pintype "passive"))
    )
    (net (code "62") (name "/RTC") (class "Default")
      (node (ref "AutoPilot V1.8") (pin "7") (pinfunction "PC13-TAMPER-RTC_7") (pintype "passive"))
    )
    (net (code "63") (name "/SONIC_ECHO") (class "Default")
      (node (ref "AutoPilot V1.8") (pin "38") (pinfunction "PE7/FSMC_D4/T1ETR_38") (pintype "passive"))
      (node (ref "P15") (pin "3") (pinfunction "3_3") (pintype "passive"))
    )
    (net (code "64") (name "/SONIC_TRIG") (class "Default")
      (node (ref "AutoPilot V1.8") (pin "5") (pinfunction "PE6/TRACED3/FSMC_A22_5") (pintype "passive"))
      (node (ref "P15") (pin "2") (pinfunction "2_2") (pintype "passive"))
    )
    (net (code "65") (name "/SWCLK") (class "Default")
      (node (ref "AutoPilot V1.8") (pin "76") (pinfunction "PA14/JTCK/SWCLK_76") (pintype "passive"))
      (node (ref "P13") (pin "3") (pinfunction "3_3") (pintype "passive"))
    )
    (net (code "66") (name "/SWDIO") (class "Default")
      (node (ref "AutoPilot V1.8") (pin "72") (pinfunction "PA13/JTMS/SWDIO_72") (pintype "passive"))
      (node (ref "P13") (pin "2") (pinfunction "2_2") (pintype "passive"))
    )
    (net (code "67") (name "GND") (class "Default")
      (node (ref "AutoPilot V1.8") (pin "10") (pinfunction "VSS_5_10") (pintype "passive"))
      (node (ref "AutoPilot V1.8") (pin "19") (pinfunction "VSSA_19") (pintype "passive"))
      (node (ref "AutoPilot V1.8") (pin "20") (pinfunction "VREF-_20") (pintype "passive"))
      (node (ref "AutoPilot V1.8") (pin "27") (pinfunction "VSS_4_27") (pintype "passive"))
      (node (ref "AutoPilot V1.8") (pin "49") (pinfunction "VSS_1_49") (pintype "passive"))
      (node (ref "AutoPilot V1.8") (pin "74") (pinfunction "VSS_2_74") (pintype "passive"))
      (node (ref "AutoPilot V1.8") (pin "99") (pinfunction "VSS_3_99") (pintype "passive"))
      (node (ref "C1") (pin "1") (pinfunction "1_1") (pintype "passive"))
      (node (ref "C10") (pin "1") (pinfunction "1_1") (pintype "passive"))
      (node (ref "C11") (pin "1") (pinfunction "1_1") (pintype "passive"))
      (node (ref "C12") (pin "1") (pinfunction "1_1") (pintype "passive"))
      (node (ref "C13") (pin "1") (pinfunction "1_1") (pintype "passive"))
      (node (ref "C14") (pin "2") (pinfunction "2_2") (pintype "passive"))
      (node (ref "C15") (pin "2") (pinfunction "2_2") (pintype "passive"))
      (node (ref "C16") (pin "2") (pinfunction "2_2") (pintype "passive"))
      (node (ref "C2") (pin "1") (pinfunction "1_1") (pintype "passive"))
      (node (ref "C3") (pin "1") (pinfunction "1_1") (pintype "passive"))
      (node (ref "C4") (pin "1") (pinfunction "1_1") (pintype "passive"))
      (node (ref "C5") (pin "1") (pinfunction "1_1") (pintype "passive"))
      (node (ref "C6") (pin "2") (pinfunction "2_2") (pintype "passive"))
      (node (ref "C7") (pin "2") (pinfunction "2_2") (pintype "passive"))
      (node (ref "C8") (pin "1") (pinfunction "1_1") (pintype "passive"))
      (node (ref "C9") (pin "1") (pinfunction "1_1") (pintype "passive"))
      (node (ref "P0") (pin "1") (pinfunction "1_1") (pintype "passive"))
      (node (ref "P1") (pin "3") (pinfunction "3_3") (pintype "passive"))
      (node (ref "P10") (pin "4") (pinfunction "4_4") (pintype "passive"))
      (node (ref "P11") (pin "2") (pinfunction "2_2") (pintype "passive"))
      (node (ref "P12") (pin "4") (pinfunction "4_4") (pintype "passive"))
      (node (ref "P13") (pin "1") (pinfunction "1_1") (pintype "passive"))
      (node (ref "P14") (pin "2") (pinfunction "2_2") (pintype "passive"))
      (node (ref "P14") (pin "4") (pinfunction "4_4") (pintype "passive"))
      (node (ref "P14") (pin "6") (pinfunction "6_6") (pintype "passive"))
      (node (ref "P14") (pin "8") (pinfunction "8_8") (pintype "passive"))
      (node (ref "P15") (pin "4") (pinfunction "4_4") (pintype "passive"))
      (node (ref "P16") (pin "4") (pinfunction "4_4") (pintype "passive"))
      (node (ref "P2") (pin "3") (pinfunction "3_3") (pintype "passive"))
      (node (ref "P3") (pin "3") (pinfunction "3_3") (pintype "passive"))
      (node (ref "P4") (pin "3") (pinfunction "3_3") (pintype "passive"))
      (node (ref "P5") (pin "2") (pinfunction "2_2") (pintype "passive"))
      (node (ref "P6") (pin "2") (pinfunction "2_2") (pintype "passive"))
      (node (ref "P7") (pin "5") (pinfunction "5_5") (pintype "passive"))
      (node (ref "P7") (pin "6") (pinfunction "6_6") (pintype "passive"))
      (node (ref "P9") (pin "1") (pinfunction "1_1") (pintype "passive"))
      (node (ref "R12") (pin "1") (pinfunction "1_1") (pintype "passive"))
      (node (ref "U0") (pin "4") (pinfunction "GND_4") (pintype "passive"))
      (node (ref "U1") (pin "11") (pinfunction "GND_11") (pintype "passive"))
      (node (ref "U1") (pin "5") (pinfunction "GND_5") (pintype "passive"))
      (node (ref "U2") (pin "1") (pinfunction "GND_1") (pintype "passive"))
    )
    (net (code "68") (name "Net-(D1-A)") (class "Default")
      (node (ref "D1") (pin "1") (pinfunction "A_1") (pintype "passive"))
      (node (ref "R1") (pin "2") (pinfunction "2_2") (pintype "passive"))
    )
    (net (code "69") (name "Net-(D2-A)") (class "Default")
      (node (ref "D2") (pin "1") (pinfunction "A_1") (pintype "passive"))
      (node (ref "R2") (pin "2") (pinfunction "2_2") (pintype "passive"))
    )
    (net (code "70") (name "Net-(D3-A)") (class "Default")
      (node (ref "D3") (pin "1") (pinfunction "A_1") (pintype "passive"))
      (node (ref "R3") (pin "2") (pinfunction "2_2") (pintype "passive"))
    )
    (net (code "71") (name "Net-(D4-A)") (class "Default")
      (node (ref "D4") (pin "1") (pinfunction "A_1") (pintype "passive"))
      (node (ref "R16") (pin "2") (pinfunction "2_2") (pintype "passive"))
    )
    (net (code "72") (name "Net-(Q1-B)") (class "Default")
      (node (ref "Q1") (pin "1") (pinfunction "B_1") (pintype "passive"))
      (node (ref "R4") (pin "1") (pinfunction "1_1") (pintype "passive"))
    )
    (net (code "73") (name "Net-(Q2-B)") (class "Default")
      (node (ref "Q2") (pin "1") (pinfunction "B_1") (pintype "passive"))
      (node (ref "R6") (pin "1") (pinfunction "1_1") (pintype "passive"))
    )
    (net (code "74") (name "Net-(Q3-B)") (class "Default")
      (node (ref "Q3") (pin "1") (pinfunction "B_1") (pintype "passive"))
      (node (ref "R8") (pin "1") (pinfunction "1_1") (pintype "passive"))
    )
    (net (code "75") (name "Net-(Q4-B)") (class "Default")
      (node (ref "Q4") (pin "1") (pinfunction "B_1") (pintype "passive"))
      (node (ref "R10") (pin "1") (pinfunction "1_1") (pintype "passive"))
    )
    (net (code "76") (name "Net-(R13-Pad2)") (class "Default")
      (node (ref "R13") (pin "2") (pinfunction "2_2") (pintype "passive"))
      (node (ref "R14") (pin "1") (pinfunction "1_1") (pintype "passive"))
    )
    (net (code "77") (name "Net-(R14-Pad2)") (class "Default")
      (node (ref "R14") (pin "2") (pinfunction "2_2") (pintype "passive"))
      (node (ref "R15") (pin "1") (pinfunction "1_1") (pintype "passive"))
    )
    (net (code "78") (name "VCC") (class "Default")
      (node (ref "C12") (pin "2") (pinfunction "2_2") (pintype "passive"))
      (node (ref "C14") (pin "1") (pinfunction "1_1") (pintype "passive"))
      (node (ref "P1") (pin "1") (pinfunction "1_1") (pintype "passive"))
      (node (ref "P15") (pin "1") (pinfunction "1_1") (pintype "passive"))
      (node (ref "P2") (pin "1") (pinfunction "1_1") (pintype "passive"))
      (node (ref "P3") (pin "1") (pinfunction "1_1") (pintype "passive"))
      (node (ref "P4") (pin "1") (pinfunction "1_1") (pintype "passive"))
      (node (ref "R11") (pin "2") (pinfunction "2_2") (pintype "passive"))
      (node (ref "R5") (pin "2") (pinfunction "2_2") (pintype "passive"))
      (node (ref "R7") (pin "2") (pinfunction "2_2") (pintype "passive"))
      (node (ref "R9") (pin "2") (pinfunction "2_2") (pintype "passive"))
      (node (ref "U2") (pin "3") (pinfunction "IN_3") (pintype "passive"))
    )
    (net (code "79") (name "VCC3.3") (class "Default")
      (node (ref "AutoPilot V1.8") (pin "100") (pinfunction "VDD_3_100") (pintype "passive"))
      (node (ref "AutoPilot V1.8") (pin "11") (pinfunction "VDD_5_11") (pintype "passive"))
      (node (ref "AutoPilot V1.8") (pin "21") (pinfunction "VREF+_21") (pintype "passive"))
      (node (ref "AutoPilot V1.8") (pin "22") (pinfunction "VDDA_22") (pintype "passive"))
      (node (ref "AutoPilot V1.8") (pin "28") (pinfunction "VDD_4_28") (pintype "passive"))
      (node (ref "AutoPilot V1.8") (pin "50") (pinfunction "VDD_1_50") (pintype "passive"))
      (node (ref "AutoPilot V1.8") (pin "6") (pinfunction "VBAT_6") (pintype "passive"))
      (node (ref "AutoPilot V1.8") (pin "75") (pinfunction "VDD_2_75") (pintype "passive"))
      (node (ref "C1") (pin "2") (pinfunction "2_2") (pintype "passive"))
      (node (ref "C13") (pin "2") (pinfunction "2_2") (pintype "passive"))
      (node (ref "C15") (pin "1") (pinfunction "1_1") (pintype "passive"))
      (node (ref "C2") (pin "2") (pinfunction "2_2") (pintype "passive"))
      (node (ref "C3") (pin "2") (pinfunction "2_2") (pintype "passive"))
      (node (ref "C4") (pin "2") (pinfunction "2_2") (pintype "passive"))
      (node (ref "C5") (pin "2") (pinfunction "2_2") (pintype "passive"))
      (node (ref "C6") (pin "1") (pinfunction "1_1") (pintype "passive"))
      (node (ref "C7") (pin "1") (pinfunction "1_1") (pintype "passive"))
      (node (ref "P0") (pin "2") (pinfunction "2_2") (pintype "passive"))
      (node (ref "P10") (pin "1") (pinfunction "1_1") (pintype "passive"))
      (node (ref "P11") (pin "1") (pinfunction "1_1") (pintype "passive"))
      (node (ref "P12") (pin "1") (pinfunction "1_1") (pintype "passive"))
      (node (ref "P16") (pin "1") (pinfunction "1_1") (pintype "passive"))
      (node (ref "P5") (pin "1") (pinfunction "1_1") (pintype "passive"))
      (node (ref "P6") (pin "1") (pinfunction "1_1") (pintype "passive"))
      (node (ref "P7") (pin "1") (pinfunction "1_1") (pintype "passive"))
      (node (ref "P7") (pin "2") (pinfunction "2_2") (pintype "passive"))
      (node (ref "R1") (pin "1") (pinfunction "1_1") (pintype "passive"))
      (node (ref "R10") (pin "2") (pinfunction "2_2") (pintype "passive"))
      (node (ref "R16") (pin "1") (pinfunction "1_1") (pintype "passive"))
      (node (ref "R17") (pin "1") (pinfunction "1_1") (pintype "passive"))
      (node (ref "R18") (pin "1") (pinfunction "1_1") (pintype "passive"))
      (node (ref "R2") (pin "1") (pinfunction "1_1") (pintype "passive"))
      (node (ref "R3") (pin "1") (pinfunction "1_1") (pintype "passive"))
      (node (ref "R4") (pin "2") (pinfunction "2_2") (pintype "passive"))
      (node (ref "R6") (pin "2") (pinfunction "2_2") (pintype "passive"))
      (node (ref "R8") (pin "2") (pinfunction "2_2") (pintype "passive"))
      (node (ref "U0") (pin "8") (pinfunction "VCC_8") (pintype "passive"))
      (node (ref "U1") (pin "2") (pinfunction "VCC_2") (pintype "passive"))
      (node (ref "U1") (pin "8") (pinfunction "VCC_8") (pintype "passive"))
      (node (ref "U2") (pin "2") (pinfunction "OUT_2") (pintype "passive"))
    )
    (net (code "80") (name "unconnected-(AutoPilot V1.8-NC-Pad73)") (class "Default")
      (node (ref "AutoPilot V1.8") (pin "73") (pinfunction "NC_73") (pintype "passive"))
    )
    (net (code "81") (name "unconnected-(AutoPilot V1.8-PA0{slash}WKUP{slash}ADC123_IN0{slash}T2C1ETR{slash}T5C1{slash}T8ETR-Pad23)") (class "Default")
      (node (ref "AutoPilot V1.8") (pin "23") (pinfunction "PA0/WKUP/ADC123_IN0/T2C1ETR/T5C1/T8ETR_23") (pintype "passive"))
    )
    (net (code "82") (name "unconnected-(AutoPilot V1.8-PA2{slash}ADC123_IN2{slash}USART2_Tx{slash}T5C3{slash}T2C3-Pad25)") (class "Default")
      (node (ref "AutoPilot V1.8") (pin "25") (pinfunction "PA2/ADC123_IN2/USART2_Tx/T5C3/T2C3_25") (pintype "passive"))
    )
    (net (code "83") (name "unconnected-(AutoPilot V1.8-PA3{slash}ADC123_IN3{slash}USART2_Rx{slash}T5C4{slash}T2C4-Pad26)") (class "Default")
      (node (ref "AutoPilot V1.8") (pin "26") (pinfunction "PA3/ADC123_IN3/USART2_Rx/T5C4/T2C4_26") (pintype "passive"))
    )
    (net (code "84") (name "unconnected-(AutoPilot V1.8-PA8{slash}T1C1{slash}MCO-Pad67)") (class "Default")
      (node (ref "AutoPilot V1.8") (pin "67") (pinfunction "PA8/T1C1/MCO_67") (pintype "passive"))
    )
    (net (code "85") (name "unconnected-(AutoPilot V1.8-PA15{slash}JTDI{slash}I2S3_WS{slash}JTDI{slash}T2C1ETR{slash}SPI3_NSS-Pad77)") (class "Default")
      (node (ref "AutoPilot V1.8") (pin "77") (pinfunction "PA15/JTDI/I2S3_WS/JTDI/T2C1ETR/SPI3_NSS_77") (pintype "passive"))
    )
    (net (code "86") (name "unconnected-(AutoPilot V1.8-PB0{slash}ADC123_IN8{slash}T3C3{slash}T8C2N{slash}T1C2N-Pad35)") (class "Default")
      (node (ref "AutoPilot V1.8") (pin "35") (pinfunction "PB0/ADC123_IN8/T3C3/T8C2N/T1C2N_35") (pintype "passive"))
    )
    (net (code "87") (name "unconnected-(AutoPilot V1.8-PB1{slash}ADC123_IN9{slash}T3C4{slash}T8C3N{slash}T1C3N-Pad36)") (class "Default")
      (node (ref "AutoPilot V1.8") (pin "36") (pinfunction "PB1/ADC123_IN9/T3C4/T8C3N/T1C3N_36") (pintype "passive"))
    )
    (net (code "88") (name "unconnected-(AutoPilot V1.8-PB3{slash}JTDO{slash}SPI3_SCK{slash}I2S3_CK{slash}T2C2{slash}SPI1_SCK-Pad89)") (class "Default")
      (node (ref "AutoPilot V1.8") (pin "89") (pinfunction "PB3/JTDO/SPI3_SCK/I2S3_CK/T2C2/SPI1_SCK_89") (pintype "passive"))
    )
    (net (code "89") (name "unconnected-(AutoPilot V1.8-PB4{slash}NJTRST{slash}SPI3_MISO{slash}T3C1{slash}SPI1_MISO-Pad90)") (class "Default")
      (node (ref "AutoPilot V1.8") (pin "90") (pinfunction "PB4/NJTRST/SPI3_MISO/T3C1/SPI1_MISO_90") (pintype "passive"))
    )
    (net (code "90") (name "unconnected-(AutoPilot V1.8-PB5{slash}I2C1_SMBA{slash}I2S3_SD{slash}SPI3_MOSI{slash}T3C2{slash}SPI1_MOSI-Pad91)") (class "Default")
      (node (ref "AutoPilot V1.8") (pin "91") (pinfunction "PB5/I2C1_SMBA/I2S3_SD/SPI3_MOSI/T3C2/SPI1_MOSI_91") (pintype "passive"))
    )
    (net (code "91") (name "unconnected-(AutoPilot V1.8-PB8{slash}SDIO_D4{slash}I2C1_SCL{slash}T4C3(7){slash}CAN_Rx-Pad95)") (class "Default")
      (node (ref "AutoPilot V1.8") (pin "95") (pinfunction "PB8/SDIO_D4/I2C1_SCL/T4C3(7)/CAN_Rx_95") (pintype "passive"))
    )
    (net (code "92") (name "unconnected-(AutoPilot V1.8-PB9{slash}SDIO_D5{slash}I2C1_SDA{slash}T4C4{slash}CAN_Tx-Pad96)") (class "Default")
      (node (ref "AutoPilot V1.8") (pin "96") (pinfunction "PB9/SDIO_D5/I2C1_SDA/T4C4/CAN_Tx_96") (pintype "passive"))
    )
    (net (code "93") (name "unconnected-(AutoPilot V1.8-PC12{slash}UART5_Tx{slash}SDIO_CK-Pad80)") (class "Default")
      (node (ref "AutoPilot V1.8") (pin "80") (pinfunction "PC12/UART5_Tx/SDIO_CK_80") (pintype "passive"))
    )
    (net (code "94") (name "unconnected-(AutoPilot V1.8-PD0{slash}CAN_Rx{slash}FSMC_D2-Pad81)") (class "Default")
      (node (ref "AutoPilot V1.8") (pin "81") (pinfunction "PD0/CAN_Rx/FSMC_D2_81") (pintype "passive"))
    )
    (net (code "95") (name "unconnected-(AutoPilot V1.8-PD1{slash}CAN_Tx{slash}FSMC_D3-Pad82)") (class "Default")
      (node (ref "AutoPilot V1.8") (pin "82") (pinfunction "PD1/CAN_Tx/FSMC_D3_82") (pintype "passive"))
    )
    (net (code "96") (name "unconnected-(AutoPilot V1.8-PD2{slash}UART5_Rx{slash}T3ETR{slash}SDIO_CMD-Pad83)") (class "Default")
      (node (ref "AutoPilot V1.8") (pin "83") (pinfunction "PD2/UART5_Rx/T3ETR/SDIO_CMD_83") (pintype "passive"))
    )
    (net (code "97") (name "unconnected-(AutoPilot V1.8-PD3{slash}FSMC_CLK-Pad84)") (class "Default")
      (node (ref "AutoPilot V1.8") (pin "84") (pinfunction "PD3/FSMC_CLK_84") (pintype "passive"))
    )
    (net (code "98") (name "unconnected-(AutoPilot V1.8-PD4{slash}FSMC_NOE-Pad85)") (class "Default")
      (node (ref "AutoPilot V1.8") (pin "85") (pinfunction "PD4/FSMC_NOE_85") (pintype "passive"))
    )
    (net (code "99") (name "unconnected-(AutoPilot V1.8-PD7{slash}FSMC_NE1{slash}FSMC_NCE2-Pad88)") (class "Default")
      (node (ref "AutoPilot V1.8") (pin "88") (pinfunction "PD7/FSMC_NE1/FSMC_NCE2_88") (pintype "passive"))
    )
    (net (code "100") (name "unconnected-(AutoPilot V1.8-PD12{slash}T4C1{slash}FSMC_A17-Pad59)") (class "Default")
      (node (ref "AutoPilot V1.8") (pin "59") (pinfunction "PD12/T4C1/FSMC_A17_59") (pintype "passive"))
    )
    (net (code "101") (name "unconnected-(AutoPilot V1.8-PD13{slash}T4C2{slash}FSMC_A18-Pad60)") (class "Default")
      (node (ref "AutoPilot V1.8") (pin "60") (pinfunction "PD13/T4C2/FSMC_A18_60") (pintype "passive"))
    )
    (net (code "102") (name "unconnected-(AutoPilot V1.8-PD14{slash}T4C3{slash}FSMC_D0-Pad61)") (class "Default")
      (node (ref "AutoPilot V1.8") (pin "61") (pinfunction "PD14/T4C3/FSMC_D0_61") (pintype "passive"))
    )
    (net (code "103") (name "unconnected-(AutoPilot V1.8-PD15{slash}T4C4{slash}FSMC_D1-Pad62)") (class "Default")
      (node (ref "AutoPilot V1.8") (pin "62") (pinfunction "PD15/T4C4/FSMC_D1_62") (pintype "passive"))
    )
    (net (code "104") (name "unconnected-(P9-Pad2)") (class "Default")
      (node (ref "P9") (pin "2") (pinfunction "2_2") (pintype "passive"))
    )
    (net (code "105") (name "unconnected-(P9-Pad3)") (class "Default")
      (node (ref "P9") (pin "3") (pinfunction "3_3") (pintype "passive"))
    )
    (net (code "106") (name "unconnected-(U1-D0-Pad1)") (class "Default")
      (node (ref "U1") (pin "1") (pinfunction "D0_1") (pintype "passive"))
    )
    (net (code "107") (name "unconnected-(U1-D2-Pad7)") (class "Default")
      (node (ref "U1") (pin "7") (pinfunction "D2_7") (pintype "passive"))
    )
    (net (code "108") (name "unconnected-(U1-D3-Pad12)") (class "Default")
      (node (ref "U1") (pin "12") (pinfunction "D3_12") (pintype "passive"))
    )
    (net (code "109") (name "unconnected-(U2-OUT-Pad4)") (class "Default")
      (node (ref "U2") (pin "4") (pinfunction "OUT_4") (pintype "passive"))
    )
    (net (code "110") (name "unconnected-(Y1-Pad3)") (class "Default")
      (node (ref "Y1") (pin "3") (pinfunction "3_3") (pintype "passive"))
    )
  )
)
